# Lenovo_P15_17.net
KiCad netlist of a schematic drawn in EAGLE
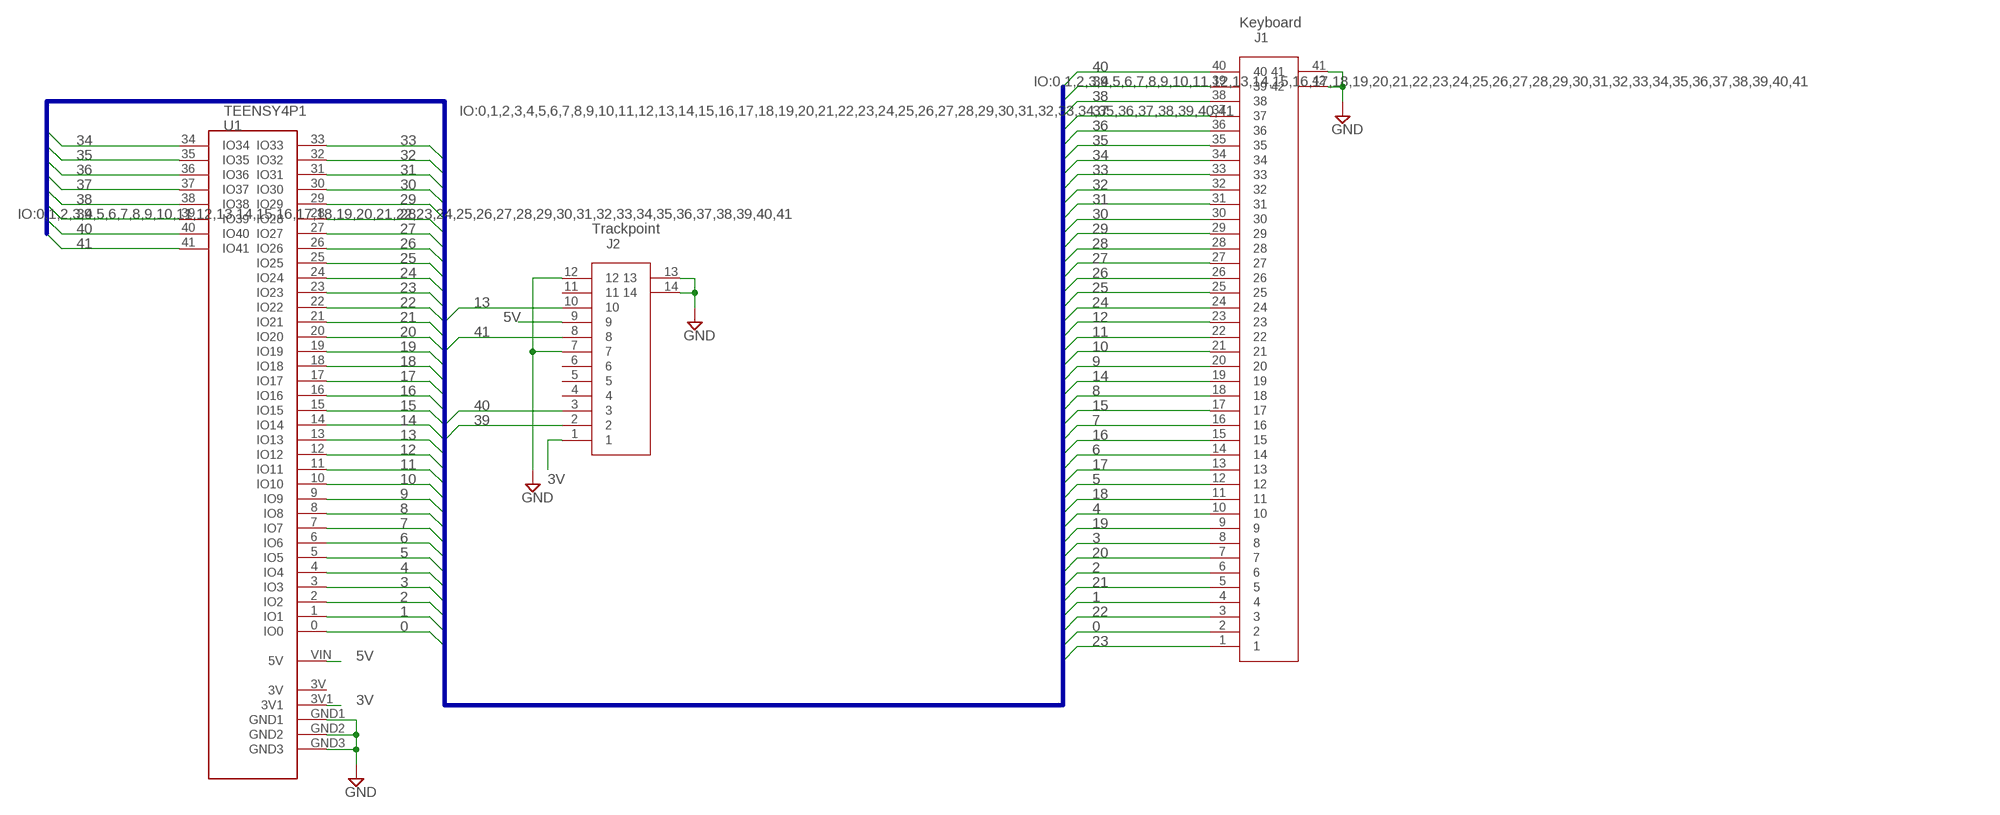
[diagram p0: schematic, sheet 1]

(export (version "E")
  (design (tool "Eeschema 10.0.6"))
  (components
    (comp (ref "J1")
      (value "FPC34_P5MM")
      (footprint "eagle-import:FPC34_P5MM")
      (libsource (lib "eagle-import") (part "FPC34_P5MM"))
    )
    (comp (ref "J2")
      (value "FPC12")
      (footprint "eagle-import:FPC12")
      (libsource (lib "eagle-import") (part "FPC12"))
    )
    (comp (ref "U1")
      (value "TEENSY4P1")
      (footprint "eagle-import:TEENSY4P0_CUTOUT")
      (libsource (lib "eagle-import") (part "TEENSY4P1_CUTOUT"))
    )
  )
  (nets
    (net (code "2") (name "/0") (class "Default")
      (node (ref "J1") (pin "2") (pinfunction "2_2") (pintype "bidirectional"))
      (node (ref "U1") (pin "0") (pinfunction "IO0_0") (pintype "bidirectional"))
    )
    (net (code "3") (name "/1") (class "Default")
      (node (ref "J1") (pin "4") (pinfunction "4_4") (pintype "bidirectional"))
      (node (ref "U1") (pin "1") (pinfunction "IO1_1") (pintype "bidirectional"))
    )
    (net (code "4") (name "/2") (class "Default")
      (node (ref "J1") (pin "6") (pinfunction "6_6") (pintype "bidirectional"))
      (node (ref "U1") (pin "2") (pinfunction "IO2_2") (pintype "bidirectional"))
    )
    (net (code "5") (name "/3") (class "Default")
      (node (ref "J1") (pin "8") (pinfunction "8_8") (pintype "bidirectional"))
      (node (ref "U1") (pin "3") (pinfunction "IO3_3") (pintype "bidirectional"))
    )
    (net (code "6") (name "/3V") (class "Default")
      (node (ref "J2") (pin "1") (pinfunction "1_1") (pintype "bidirectional"))
      (node (ref "U1") (pin "3V1") (pinfunction "3V1_3V1") (pintype "bidirectional"))
    )
    (net (code "7") (name "/4") (class "Default")
      (node (ref "J1") (pin "10") (pinfunction "10_10") (pintype "bidirectional"))
      (node (ref "U1") (pin "4") (pinfunction "IO4_4") (pintype "bidirectional"))
    )
    (net (code "8") (name "/5") (class "Default")
      (node (ref "J1") (pin "12") (pinfunction "12_12") (pintype "bidirectional"))
      (node (ref "U1") (pin "5") (pinfunction "IO5_5") (pintype "bidirectional"))
    )
    (net (code "9") (name "/5V") (class "Default")
      (node (ref "J2") (pin "9") (pinfunction "9_9") (pintype "bidirectional"))
      (node (ref "U1") (pin "VIN") (pinfunction "5V_VIN") (pintype "bidirectional"))
    )
    (net (code "10") (name "/6") (class "Default")
      (node (ref "J1") (pin "14") (pinfunction "14_14") (pintype "bidirectional"))
      (node (ref "U1") (pin "6") (pinfunction "IO6_6") (pintype "bidirectional"))
    )
    (net (code "11") (name "/7") (class "Default")
      (node (ref "J1") (pin "16") (pinfunction "16_16") (pintype "bidirectional"))
      (node (ref "U1") (pin "7") (pinfunction "IO7_7") (pintype "bidirectional"))
    )
    (net (code "12") (name "/8") (class "Default")
      (node (ref "J1") (pin "18") (pinfunction "18_18") (pintype "bidirectional"))
      (node (ref "U1") (pin "8") (pinfunction "IO8_8") (pintype "bidirectional"))
    )
    (net (code "13") (name "/9") (class "Default")
      (node (ref "J1") (pin "20") (pinfunction "20_20") (pintype "bidirectional"))
      (node (ref "U1") (pin "9") (pinfunction "IO9_9") (pintype "bidirectional"))
    )
    (net (code "14") (name "/10") (class "Default")
      (node (ref "J1") (pin "21") (pinfunction "21_21") (pintype "bidirectional"))
      (node (ref "U1") (pin "10") (pinfunction "IO10_10") (pintype "bidirectional"))
    )
    (net (code "15") (name "/11") (class "Default")
      (node (ref "J1") (pin "22") (pinfunction "22_22") (pintype "bidirectional"))
      (node (ref "U1") (pin "11") (pinfunction "IO11_11") (pintype "bidirectional"))
    )
    (net (code "16") (name "/12") (class "Default")
      (node (ref "J1") (pin "23") (pinfunction "23_23") (pintype "bidirectional"))
      (node (ref "U1") (pin "12") (pinfunction "IO12_12") (pintype "bidirectional"))
    )
    (net (code "17") (name "/13") (class "Default")
      (node (ref "J2") (pin "10") (pinfunction "10_10") (pintype "bidirectional"))
      (node (ref "U1") (pin "13") (pinfunction "IO13_13") (pintype "bidirectional"))
    )
    (net (code "18") (name "/14") (class "Default")
      (node (ref "J1") (pin "19") (pinfunction "19_19") (pintype "bidirectional"))
      (node (ref "U1") (pin "14") (pinfunction "IO14_14") (pintype "bidirectional"))
    )
    (net (code "19") (name "/15") (class "Default")
      (node (ref "J1") (pin "17") (pinfunction "17_17") (pintype "bidirectional"))
      (node (ref "U1") (pin "15") (pinfunction "IO15_15") (pintype "bidirectional"))
    )
    (net (code "20") (name "/16") (class "Default")
      (node (ref "J1") (pin "15") (pinfunction "15_15") (pintype "bidirectional"))
      (node (ref "U1") (pin "16") (pinfunction "IO16_16") (pintype "bidirectional"))
    )
    (net (code "21") (name "/17") (class "Default")
      (node (ref "J1") (pin "13") (pinfunction "13_13") (pintype "bidirectional"))
      (node (ref "U1") (pin "17") (pinfunction "IO17_17") (pintype "bidirectional"))
    )
    (net (code "22") (name "/18") (class "Default")
      (node (ref "J1") (pin "11") (pinfunction "11_11") (pintype "bidirectional"))
      (node (ref "U1") (pin "18") (pinfunction "IO18_18") (pintype "bidirectional"))
    )
    (net (code "23") (name "/19") (class "Default")
      (node (ref "J1") (pin "9") (pinfunction "9_9") (pintype "bidirectional"))
      (node (ref "U1") (pin "19") (pinfunction "IO19_19") (pintype "bidirectional"))
    )
    (net (code "24") (name "/20") (class "Default")
      (node (ref "J1") (pin "7") (pinfunction "7_7") (pintype "bidirectional"))
      (node (ref "U1") (pin "20") (pinfunction "IO20_20") (pintype "bidirectional"))
    )
    (net (code "25") (name "/21") (class "Default")
      (node (ref "J1") (pin "5") (pinfunction "5_5") (pintype "bidirectional"))
      (node (ref "U1") (pin "21") (pinfunction "IO21_21") (pintype "bidirectional"))
    )
    (net (code "26") (name "/22") (class "Default")
      (node (ref "J1") (pin "3") (pinfunction "3_3") (pintype "bidirectional"))
      (node (ref "U1") (pin "22") (pinfunction "IO22_22") (pintype "bidirectional"))
    )
    (net (code "27") (name "/23") (class "Default")
      (node (ref "J1") (pin "1") (pinfunction "1_1") (pintype "bidirectional"))
      (node (ref "U1") (pin "23") (pinfunction "IO23_23") (pintype "bidirectional"))
    )
    (net (code "28") (name "/24") (class "Default")
      (node (ref "J1") (pin "24") (pinfunction "24_24") (pintype "bidirectional"))
      (node (ref "U1") (pin "24") (pinfunction "IO24_24") (pintype "bidirectional"))
    )
    (net (code "29") (name "/25") (class "Default")
      (node (ref "J1") (pin "25") (pinfunction "25_25") (pintype "bidirectional"))
      (node (ref "U1") (pin "25") (pinfunction "IO25_25") (pintype "bidirectional"))
    )
    (net (code "30") (name "/26") (class "Default")
      (node (ref "J1") (pin "26") (pinfunction "26_26") (pintype "bidirectional"))
      (node (ref "U1") (pin "26") (pinfunction "IO26_26") (pintype "bidirectional"))
    )
    (net (code "31") (name "/27") (class "Default")
      (node (ref "J1") (pin "27") (pinfunction "27_27") (pintype "bidirectional"))
      (node (ref "U1") (pin "27") (pinfunction "IO27_27") (pintype "bidirectional"))
    )
    (net (code "32") (name "/28") (class "Default")
      (node (ref "J1") (pin "28") (pinfunction "28_28") (pintype "bidirectional"))
      (node (ref "U1") (pin "28") (pinfunction "IO28_28") (pintype "bidirectional"))
    )
    (net (code "33") (name "/29") (class "Default")
      (node (ref "J1") (pin "29") (pinfunction "29_29") (pintype "bidirectional"))
      (node (ref "U1") (pin "29") (pinfunction "IO29_29") (pintype "bidirectional"))
    )
    (net (code "34") (name "/30") (class "Default")
      (node (ref "J1") (pin "30") (pinfunction "30_30") (pintype "bidirectional"))
      (node (ref "U1") (pin "30") (pinfunction "IO30_30") (pintype "bidirectional"))
    )
    (net (code "35") (name "/31") (class "Default")
      (node (ref "J1") (pin "31") (pinfunction "31_31") (pintype "bidirectional"))
      (node (ref "U1") (pin "31") (pinfunction "IO31_31") (pintype "bidirectional"))
    )
    (net (code "36") (name "/32") (class "Default")
      (node (ref "J1") (pin "32") (pinfunction "32_32") (pintype "bidirectional"))
      (node (ref "U1") (pin "32") (pinfunction "IO32_32") (pintype "bidirectional"))
    )
    (net (code "37") (name "/33") (class "Default")
      (node (ref "J1") (pin "33") (pinfunction "33_33") (pintype "bidirectional"))
      (node (ref "U1") (pin "33") (pinfunction "IO33_33") (pintype "bidirectional"))
    )
    (net (code "38") (name "/34") (class "Default")
      (node (ref "J1") (pin "34") (pinfunction "34_34") (pintype "bidirectional"))
      (node (ref "U1") (pin "34") (pinfunction "IO34_34") (pintype "bidirectional"))
    )
    (net (code "39") (name "/35") (class "Default")
      (node (ref "J1") (pin "35") (pinfunction "35_35") (pintype "bidirectional"))
      (node (ref "U1") (pin "35") (pinfunction "IO35_35") (pintype "bidirectional"))
    )
    (net (code "40") (name "/36") (class "Default")
      (node (ref "J1") (pin "36") (pinfunction "36_36") (pintype "bidirectional"))
      (node (ref "U1") (pin "36") (pinfunction "IO36_36") (pintype "bidirectional"))
    )
    (net (code "41") (name "/37") (class "Default")
      (node (ref "J1") (pin "37") (pinfunction "37_37") (pintype "bidirectional"))
      (node (ref "U1") (pin "37") (pinfunction "IO37_37") (pintype "bidirectional"))
    )
    (net (code "42") (name "/38") (class "Default")
      (node (ref "J1") (pin "38") (pinfunction "38_38") (pintype "bidirectional"))
      (node (ref "U1") (pin "38") (pinfunction "IO38_38") (pintype "bidirectional"))
    )
    (net (code "43") (name "/39") (class "Default")
      (node (ref "J1") (pin "39") (pinfunction "39_39") (pintype "bidirectional"))
      (node (ref "J2") (pin "2") (pinfunction "2_2") (pintype "bidirectional"))
      (node (ref "U1") (pin "39") (pinfunction "IO39_39") (pintype "bidirectional"))
    )
    (net (code "44") (name "/41") (class "Default")
      (node (ref "J2") (pin "8") (pinfunction "8_8") (pintype "bidirectional"))
      (node (ref "U1") (pin "41") (pinfunction "IO41_41") (pintype "bidirectional"))
    )
    (net (code "45") (name "/IO:0") (class "Default")
      (node (ref "J1") (pin "40") (pinfunction "40_40") (pintype "bidirectional"))
      (node (ref "J2") (pin "3") (pinfunction "3_3") (pintype "bidirectional"))
      (node (ref "U1") (pin "40") (pinfunction "IO40_40") (pintype "bidirectional"))
    )
    (net (code "47") (name "GND") (class "Default")
      (node (ref "J1") (pin "41") (pinfunction "41_41") (pintype "bidirectional"))
      (node (ref "J1") (pin "42") (pinfunction "42_42") (pintype "bidirectional"))
      (node (ref "J2") (pin "12") (pinfunction "12_12") (pintype "bidirectional"))
      (node (ref "J2") (pin "13") (pinfunction "13_13") (pintype "bidirectional"))
      (node (ref "J2") (pin "14") (pinfunction "14_14") (pintype "bidirectional"))
      (node (ref "J2") (pin "7") (pinfunction "7_7") (pintype "bidirectional"))
      (node (ref "U1") (pin "GND1") (pinfunction "GND1_GND1") (pintype "bidirectional"))
      (node (ref "U1") (pin "GND2") (pinfunction "GND2_GND2") (pintype "bidirectional"))
      (node (ref "U1") (pin "GND3") (pinfunction "GND3_GND3") (pintype "bidirectional"))
    )
    (net (code "48") (name "unconnected-(J2-Pad4)") (class "Default")
      (node (ref "J2") (pin "4") (pinfunction "4_4") (pintype "bidirectional"))
    )
    (net (code "49") (name "unconnected-(J2-Pad5)") (class "Default")
      (node (ref "J2") (pin "5") (pinfunction "5_5") (pintype "bidirectional"))
    )
    (net (code "50") (name "unconnected-(J2-Pad6)") (class "Default")
      (node (ref "J2") (pin "6") (pinfunction "6_6") (pintype "bidirectional"))
    )
    (net (code "51") (name "unconnected-(J2-Pad11)") (class "Default")
      (node (ref "J2") (pin "11") (pinfunction "11_11") (pintype "bidirectional"))
    )
    (net (code "52") (name "unconnected-(U1-Pad3V)") (class "Default")
      (node (ref "U1") (pin "3V") (pinfunction "3V_3V") (pintype "bidirectional"))
    )
  )
)
